# Microcontroller.net
KiCad netlist of a schematic drawn in Altium Designer
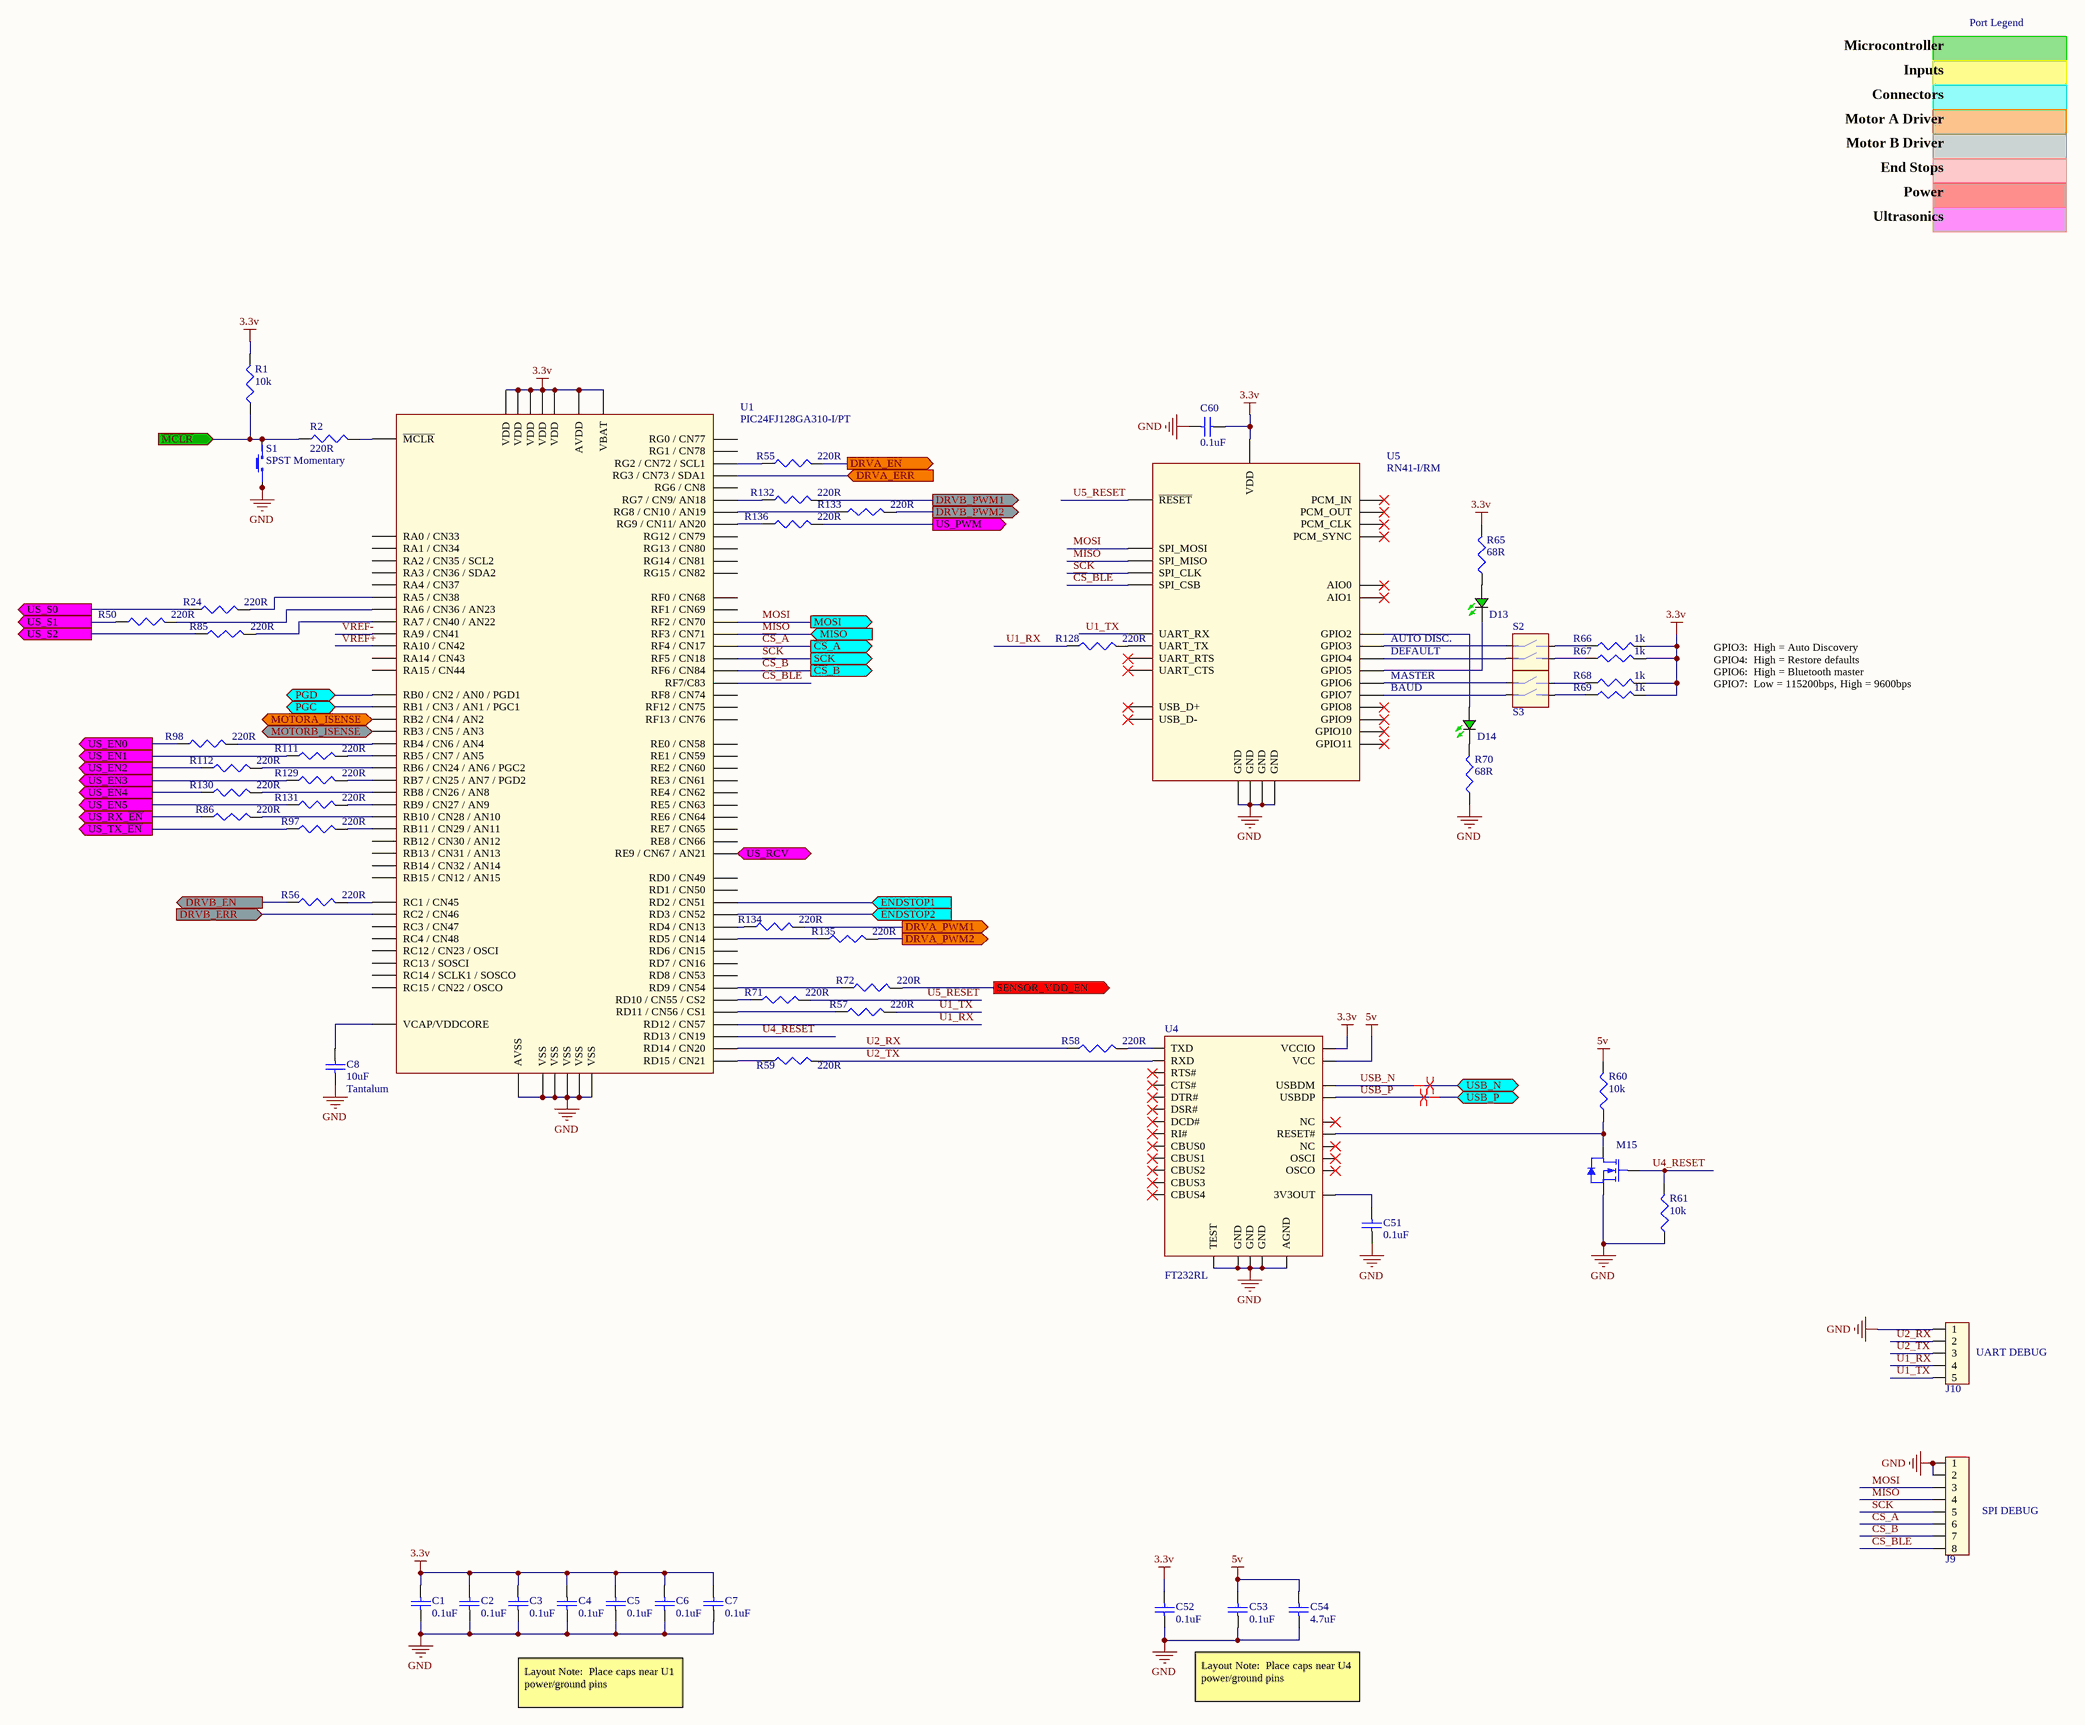
[diagram p0: Microcontroller.SchDoc]

(export (version "E")
  (design (tool "Eeschema 10.0.6"))
  (components
    (comp (ref "C1") (value "0.1uF") (footprint "CAP0603W") (libsource (lib "Altium Library") (part "0.1uF")))
    (comp (ref "C2") (value "0.1uF") (footprint "CAP0603W") (libsource (lib "Altium Library") (part "0.1uF")))
    (comp (ref "C3") (value "0.1uF") (footprint "CAP0603W") (libsource (lib "Altium Library") (part "0.1uF")))
    (comp (ref "C4") (value "0.1uF") (footprint "CAP0603W") (libsource (lib "Altium Library") (part "0.1uF")))
    (comp (ref "C5") (value "0.1uF") (footprint "CAP0603W") (libsource (lib "Altium Library") (part "0.1uF")))
    (comp (ref "C6") (value "0.1uF") (footprint "CAP0603W") (libsource (lib "Altium Library") (part "0.1uF")))
    (comp (ref "C7") (value "0.1uF") (footprint "CAP0603W") (libsource (lib "Altium Library") (part "0.1uF")))
    (comp (ref "C8")
      (value "10uF")
      (footprint "CAP1206W")
      (fields (field (name "TYPE") "Tantalum"))
      (libsource (lib "Altium Library") (part "10uF Tantalum"))
    )
    (comp (ref "C51")
      (value "0.1uF")
      (footprint "CAP0603W")
      (libsource (lib "Altium Library") (part "0.1uF"))
    )
    (comp (ref "C52")
      (value "0.1uF")
      (footprint "CAP0603W")
      (libsource (lib "Altium Library") (part "0.1uF"))
    )
    (comp (ref "C53")
      (value "0.1uF")
      (footprint "CAP0603W")
      (libsource (lib "Altium Library") (part "0.1uF"))
    )
    (comp (ref "C54")
      (value "4.7uF")
      (footprint "CAP1206W")
      (fields (field (name "VOLTAGE") "16v"))
      (libsource (lib "Altium Library") (part "4.7uF"))
    )
    (comp (ref "C60")
      (value "0.1uF")
      (footprint "CAP0603W")
      (libsource (lib "Altium Library") (part "0.1uF"))
    )
    (comp (ref "D13")
      (value "LTST-S270KGKT")
      (footprint "LED Green 0603")
      (fields (field (name "MFG") "Lite On"))
      (libsource (lib "Altium Library") (part "LED Green 0603"))
    )
    (comp (ref "D14")
      (value "LTST-S270KGKT")
      (footprint "LED Green 0603")
      (fields (field (name "MFG") "Lite On"))
      (libsource (lib "Altium Library") (part "LED Green 0603"))
    )
    (comp (ref "J9")
      (value "1x8 Header")
      (footprint "1x8 Header")
      (description "1x8 Header, 2.52mm pitch")
      (libsource (lib "Altium Library") (part "1x8 Header"))
    )
    (comp (ref "J10")
      (value "1x5 Header")
      (footprint "1x5 Header")
      (description "1x5 Header, 2.52mm pitch")
      (libsource (lib "Altium Library") (part "1x5 Header"))
    )
    (comp (ref "M15")
      (value "2N7002P,215")
      (footprint "SOT23-3M")
      (description "NFET_SINGLE_360mA_60V")
      (fields (field (name "MFG") "NXP"))
      (libsource (lib "Altium Library") (part "2N7002"))
    )
    (comp (ref "R1")
      (value "10k")
      (footprint "RES0603W")
      (fields (field (name "TOLERANCE") "1%") (field (name "POWER") "0.1W") (field (name "MFG") "Vishay"))
      (libsource (lib "Altium Library") (part "10K (0603)"))
    )
    (comp (ref "R2")
      (value "220R")
      (footprint "RES0603W")
      (fields (field (name "TOLERANCE") "1%") (field (name "POWER") "0.1W") (field (name "MFG") "Vishay"))
      (libsource (lib "Altium Library") (part "220R (0603)"))
    )
    (comp (ref "R24")
      (value "220R")
      (footprint "RES0603W")
      (fields (field (name "TOLERANCE") "1%") (field (name "POWER") "0.1W") (field (name "MFG") "Vishay"))
      (libsource (lib "Altium Library") (part "220R (0603)"))
    )
    (comp (ref "R50")
      (value "220R")
      (footprint "RES0603W")
      (fields (field (name "TOLERANCE") "1%") (field (name "POWER") "0.1W") (field (name "MFG") "Vishay"))
      (libsource (lib "Altium Library") (part "220R (0603)"))
    )
    (comp (ref "R55")
      (value "220R")
      (footprint "RES0603W")
      (fields (field (name "TOLERANCE") "1%") (field (name "POWER") "0.1W") (field (name "MFG") "Vishay"))
      (libsource (lib "Altium Library") (part "220R (0603)"))
    )
    (comp (ref "R56")
      (value "220R")
      (footprint "RES0603W")
      (fields (field (name "TOLERANCE") "1%") (field (name "POWER") "0.1W") (field (name "MFG") "Vishay"))
      (libsource (lib "Altium Library") (part "220R (0603)"))
    )
    (comp (ref "R57")
      (value "220R")
      (footprint "RES0603W")
      (fields (field (name "TOLERANCE") "1%") (field (name "POWER") "0.1W") (field (name "MFG") "Vishay"))
      (libsource (lib "Altium Library") (part "220R (0603)"))
    )
    (comp (ref "R58")
      (value "220R")
      (footprint "RES0603W")
      (fields (field (name "TOLERANCE") "1%") (field (name "POWER") "0.1W") (field (name "MFG") "Vishay"))
      (libsource (lib "Altium Library") (part "220R (0603)"))
    )
    (comp (ref "R59")
      (value "220R")
      (footprint "RES0603W")
      (fields (field (name "TOLERANCE") "1%") (field (name "POWER") "0.1W") (field (name "MFG") "Vishay"))
      (libsource (lib "Altium Library") (part "220R (0603)"))
    )
    (comp (ref "R60")
      (value "10k")
      (footprint "RES0603W")
      (fields (field (name "TOLERANCE") "1%") (field (name "POWER") "0.1W") (field (name "MFG") "Vishay"))
      (libsource (lib "Altium Library") (part "10K (0603)"))
    )
    (comp (ref "R61")
      (value "10k")
      (footprint "RES0603W")
      (fields (field (name "TOLERANCE") "1%") (field (name "POWER") "0.1W") (field (name "MFG") "Vishay"))
      (libsource (lib "Altium Library") (part "10K (0603)"))
    )
    (comp (ref "R65")
      (value "68R")
      (footprint "RES0603W")
      (fields (field (name "TOLERANCE") "1%") (field (name "POWER") "0.1W") (field (name "MFG") "Vishay"))
      (libsource (lib "Altium Library") (part "68R (0603)"))
    )
    (comp (ref "R66")
      (value "1k")
      (footprint "RES0603W")
      (fields (field (name "TOLERANCE") "1%") (field (name "POWER") "0.1W") (field (name "MFG") "Vishay"))
      (libsource (lib "Altium Library") (part "1k (0603)"))
    )
    (comp (ref "R67")
      (value "1k")
      (footprint "RES0603W")
      (fields (field (name "TOLERANCE") "1%") (field (name "POWER") "0.1W") (field (name "MFG") "Vishay"))
      (libsource (lib "Altium Library") (part "1k (0603)"))
    )
    (comp (ref "R68")
      (value "1k")
      (footprint "RES0603W")
      (fields (field (name "TOLERANCE") "1%") (field (name "POWER") "0.1W") (field (name "MFG") "Vishay"))
      (libsource (lib "Altium Library") (part "1k (0603)"))
    )
    (comp (ref "R69")
      (value "1k")
      (footprint "RES0603W")
      (fields (field (name "TOLERANCE") "1%") (field (name "POWER") "0.1W") (field (name "MFG") "Vishay"))
      (libsource (lib "Altium Library") (part "1k (0603)"))
    )
    (comp (ref "R70")
      (value "68R")
      (footprint "RES0603W")
      (fields (field (name "TOLERANCE") "1%") (field (name "POWER") "0.1W") (field (name "MFG") "Vishay"))
      (libsource (lib "Altium Library") (part "68R (0603)"))
    )
    (comp (ref "R71")
      (value "220R")
      (footprint "RES0603W")
      (fields (field (name "TOLERANCE") "1%") (field (name "POWER") "0.1W") (field (name "MFG") "Vishay"))
      (libsource (lib "Altium Library") (part "220R (0603)"))
    )
    (comp (ref "R72")
      (value "220R")
      (footprint "RES0603W")
      (fields (field (name "TOLERANCE") "1%") (field (name "POWER") "0.1W") (field (name "MFG") "Vishay"))
      (libsource (lib "Altium Library") (part "220R (0603)"))
    )
    (comp (ref "R85")
      (value "220R")
      (footprint "RES0603W")
      (fields (field (name "TOLERANCE") "1%") (field (name "POWER") "0.1W") (field (name "MFG") "Vishay"))
      (libsource (lib "Altium Library") (part "220R (0603)"))
    )
    (comp (ref "R86")
      (value "220R")
      (footprint "RES0603W")
      (fields (field (name "TOLERANCE") "1%") (field (name "POWER") "0.1W") (field (name "MFG") "Vishay"))
      (libsource (lib "Altium Library") (part "220R (0603)"))
    )
    (comp (ref "R97")
      (value "220R")
      (footprint "RES0603W")
      (fields (field (name "TOLERANCE") "1%") (field (name "POWER") "0.1W") (field (name "MFG") "Vishay"))
      (libsource (lib "Altium Library") (part "220R (0603)"))
    )
    (comp (ref "R98")
      (value "220R")
      (footprint "RES0603W")
      (fields (field (name "TOLERANCE") "1%") (field (name "POWER") "0.1W") (field (name "MFG") "Vishay"))
      (libsource (lib "Altium Library") (part "220R (0603)"))
    )
    (comp (ref "R111")
      (value "220R")
      (footprint "RES0603W")
      (fields (field (name "TOLERANCE") "1%") (field (name "POWER") "0.1W") (field (name "MFG") "Vishay"))
      (libsource (lib "Altium Library") (part "220R (0603)"))
    )
    (comp (ref "R112")
      (value "220R")
      (footprint "RES0603W")
      (fields (field (name "TOLERANCE") "1%") (field (name "POWER") "0.1W") (field (name "MFG") "Vishay"))
      (libsource (lib "Altium Library") (part "220R (0603)"))
    )
    (comp (ref "R128")
      (value "220R")
      (footprint "RES0603W")
      (fields (field (name "TOLERANCE") "1%") (field (name "POWER") "0.1W") (field (name "MFG") "Vishay"))
      (libsource (lib "Altium Library") (part "220R (0603)"))
    )
    (comp (ref "R129")
      (value "220R")
      (footprint "RES0603W")
      (fields (field (name "TOLERANCE") "1%") (field (name "POWER") "0.1W") (field (name "MFG") "Vishay"))
      (libsource (lib "Altium Library") (part "220R (0603)"))
    )
    (comp (ref "R130")
      (value "220R")
      (footprint "RES0603W")
      (fields (field (name "TOLERANCE") "1%") (field (name "POWER") "0.1W") (field (name "MFG") "Vishay"))
      (libsource (lib "Altium Library") (part "220R (0603)"))
    )
    (comp (ref "R131")
      (value "220R")
      (footprint "RES0603W")
      (fields (field (name "TOLERANCE") "1%") (field (name "POWER") "0.1W") (field (name "MFG") "Vishay"))
      (libsource (lib "Altium Library") (part "220R (0603)"))
    )
    (comp (ref "R132")
      (value "220R")
      (footprint "RES0603W")
      (fields (field (name "TOLERANCE") "1%") (field (name "POWER") "0.1W") (field (name "MFG") "Vishay"))
      (libsource (lib "Altium Library") (part "220R (0603)"))
    )
    (comp (ref "R133")
      (value "220R")
      (footprint "RES0603W")
      (fields (field (name "TOLERANCE") "1%") (field (name "POWER") "0.1W") (field (name "MFG") "Vishay"))
      (libsource (lib "Altium Library") (part "220R (0603)"))
    )
    (comp (ref "R134")
      (value "220R")
      (footprint "RES0603W")
      (fields (field (name "TOLERANCE") "1%") (field (name "POWER") "0.1W") (field (name "MFG") "Vishay"))
      (libsource (lib "Altium Library") (part "220R (0603)"))
    )
    (comp (ref "R135")
      (value "220R")
      (footprint "RES0603W")
      (fields (field (name "TOLERANCE") "1%") (field (name "POWER") "0.1W") (field (name "MFG") "Vishay"))
      (libsource (lib "Altium Library") (part "220R (0603)"))
    )
    (comp (ref "R136")
      (value "220R")
      (footprint "RES0603W")
      (fields (field (name "TOLERANCE") "1%") (field (name "POWER") "0.1W") (field (name "MFG") "Vishay"))
      (libsource (lib "Altium Library") (part "220R (0603)"))
    )
    (comp (ref "S1")
      (value "SPST Momentary")
      (footprint "TECONN_1571563")
      (description "SPST Momentary Switch")
      (fields (field (name "MFG") "TE Connectivity") (field (name "TYPE") "SPST Momentary"))
      (libsource (lib "Altium Library") (part "SPST Momentary"))
    )
    (comp (ref "S2")
      (value "SPST")
      (footprint "CTS_219-2MST")
      (description "SPST Microswitch Array (2 Switches)")
      (fields (field (name "MFG") "CTS"))
      (libsource (lib "Altium Library") (part "2xSPST Microswitch"))
    )
    (comp (ref "S3")
      (value "SPST")
      (footprint "CTS_219-2MST")
      (description "SPST Microswitch Array (2 Switches)")
      (fields (field (name "MFG") "CTS"))
      (libsource (lib "Altium Library") (part "2xSPST Microswitch"))
    )
    (comp (ref "U1")
      (value "PIC24FJ128GA310-I/PT")
      (footprint "TQFP100 0.4mm Pitch")
      (fields (field (name "MFG") "Microchip"))
      (libsource (lib "Altium Library") (part "PIC24FJ128GA310"))
    )
    (comp (ref "U4")
      (value "FT232RL")
      (footprint "SSOP-28")
      (description "UART Interface/Bridge")
      (fields (field (name "MFG") "FTDI"))
      (libsource (lib "Altium Library") (part "FT232RL"))
    )
    (comp (ref "U5")
      (value "RN41-I/RM")
      (footprint "RN41")
      (description "2.4GHz Class 1 Bluetooth Module")
      (fields (field (name "MFG") "MICROCHIP"))
      (libsource (lib "Altium Library") (part "RN41"))
    )
  )
  (nets
    (net (code "1") (name "/DRVA_EN") (class "Default")
      (node (ref "R55") (pin "2") (pinfunction "2_2") (pintype "passive"))
    )
    (net (code "2") (name "/DRVA_ERR") (class "Default")
      (node (ref "U1") (pin "56") (pinfunction "RG3_/_CN73_/_SDA1_56") (pintype "passive"))
    )
    (net (code "3") (name "/DRVA_PWM1") (class "Default")
      (node (ref "R134") (pin "2") (pinfunction "2_2") (pintype "passive"))
    )
    (net (code "4") (name "/DRVA_PWM2") (class "Default")
      (node (ref "R135") (pin "2") (pinfunction "2_2") (pintype "passive"))
    )
    (net (code "5") (name "/DRVB_EN") (class "Default")
      (node (ref "R56") (pin "1") (pinfunction "1_1") (pintype "passive"))
    )
    (net (code "6") (name "/DRVB_ERR") (class "Default")
      (node (ref "U1") (pin "7") (pinfunction "RC2_/_CN46_7") (pintype "passive"))
    )
    (net (code "7") (name "/DRVB_PWM1") (class "Default")
      (node (ref "R132") (pin "2") (pinfunction "2_2") (pintype "passive"))
    )
    (net (code "8") (name "/DRVB_PWM2") (class "Default")
      (node (ref "R133") (pin "2") (pinfunction "2_2") (pintype "passive"))
    )
    (net (code "9") (name "/ENDSTOP1") (class "Default")
      (node (ref "U1") (pin "77") (pinfunction "RD2_/_CN51_77") (pintype "passive"))
    )
    (net (code "10") (name "/ENDSTOP2") (class "Default")
      (node (ref "U1") (pin "78") (pinfunction "RD3_/_CN52_78") (pintype "passive"))
    )
    (net (code "11") (name "/MISO") (class "Default")
      (node (ref "J9") (pin "4") (pinfunction "4_4") (pintype "passive"))
      (node (ref "U1") (pin "51") (pinfunction "RF3_/_CN71_51") (pintype "passive"))
      (node (ref "U5") (pin "24") (pinfunction "SPI_MISO_24") (pintype "passive"))
    )
    (net (code "12") (name "/MOSI") (class "Default")
      (node (ref "J9") (pin "3") (pinfunction "3_3") (pintype "passive"))
      (node (ref "U1") (pin "52") (pinfunction "RF2_/_CN70_52") (pintype "passive"))
      (node (ref "U5") (pin "2") (pinfunction "SPI_MOSI_2") (pintype "passive"))
    )
    (net (code "13") (name "/MOTORA_ISENSE") (class "Default")
      (node (ref "U1") (pin "23") (pinfunction "RB2_/_CN4_/_AN2_23") (pintype "passive"))
    )
    (net (code "14") (name "/MOTORB_ISENSE") (class "Default")
      (node (ref "U1") (pin "22") (pinfunction "RB3_/_CN5_/_AN3_22") (pintype "passive"))
    )
    (net (code "15") (name "/PGC") (class "Default")
      (node (ref "U1") (pin "24") (pinfunction "RB1_/_CN3_/_AN1_/_PGC1_24") (pintype "passive"))
    )
    (net (code "16") (name "/PGD") (class "Default")
      (node (ref "U1") (pin "25") (pinfunction "RB0_/_CN2_/_AN0_/_PGD1_25") (pintype "passive"))
    )
    (net (code "17") (name "/SCK") (class "Default")
      (node (ref "J9") (pin "5") (pinfunction "5_5") (pintype "passive"))
      (node (ref "U1") (pin "50") (pinfunction "RF5_/_CN18_50") (pintype "passive"))
      (node (ref "U5") (pin "6") (pinfunction "SPI_CLK_6") (pintype "passive"))
    )
    (net (code "18") (name "/SENSOR_VDD_EN") (class "Default")
      (node (ref "R72") (pin "2") (pinfunction "2_2") (pintype "passive"))
    )
    (net (code "19") (name "/U1_RX") (class "Default")
      (node (ref "J10") (pin "4") (pinfunction "4_4") (pintype "passive"))
      (node (ref "R128") (pin "1") (pinfunction "1_1") (pintype "passive"))
      (node (ref "U1") (pin "79") (pinfunction "RD12_/_CN57_79") (pintype "passive"))
    )
    (net (code "20") (name "/U1_TX") (class "Default")
      (node (ref "J10") (pin "5") (pinfunction "5_5") (pintype "passive"))
      (node (ref "R57") (pin "2") (pinfunction "2_2") (pintype "passive"))
      (node (ref "U5") (pin "13") (pinfunction "UART_RX_13") (pintype "passive"))
    )
    (net (code "21") (name "/U2_RX") (class "Default")
      (node (ref "J10") (pin "2") (pinfunction "2_2") (pintype "passive"))
      (node (ref "R58") (pin "1") (pinfunction "1_1") (pintype "passive"))
      (node (ref "U1") (pin "47") (pinfunction "RD14_/_CN20_47") (pintype "passive"))
    )
    (net (code "22") (name "/U2_TX") (class "Default")
      (node (ref "J10") (pin "3") (pinfunction "3_3") (pintype "passive"))
      (node (ref "R59") (pin "2") (pinfunction "2_2") (pintype "passive"))
      (node (ref "U4") (pin "5") (pinfunction "RXD_5") (pintype "passive"))
    )
    (net (code "23") (name "/U4_RESET") (class "Default")
      (node (ref "M15") (pin "1") (pinfunction "GATE_1") (pintype "passive"))
      (node (ref "R61") (pin "2") (pinfunction "2_2") (pintype "passive"))
      (node (ref "U1") (pin "80") (pinfunction "RD13_/_CN19_80") (pintype "passive"))
    )
    (net (code "24") (name "/U5_RESET") (class "Default")
      (node (ref "R71") (pin "2") (pinfunction "2_2") (pintype "passive"))
      (node (ref "U5") (pin "5") (pinfunction "~{RESET}_5") (pintype "passive"))
    )
    (net (code "25") (name "/USB_N") (class "Default")
      (node (ref "U4") (pin "16") (pinfunction "USBDM_16") (pintype "passive"))
    )
    (net (code "26") (name "/USB_P") (class "Default")
      (node (ref "U4") (pin "15") (pinfunction "USBDP_15") (pintype "passive"))
    )
    (net (code "27") (name "/US_EN0") (class "Default")
      (node (ref "R98") (pin "1") (pinfunction "1_1") (pintype "passive"))
    )
    (net (code "28") (name "/US_EN1") (class "Default")
      (node (ref "R111") (pin "1") (pinfunction "1_1") (pintype "passive"))
    )
    (net (code "29") (name "/US_EN2") (class "Default")
      (node (ref "R112") (pin "1") (pinfunction "1_1") (pintype "passive"))
    )
    (net (code "30") (name "/US_EN3") (class "Default")
      (node (ref "R129") (pin "1") (pinfunction "1_1") (pintype "passive"))
    )
    (net (code "31") (name "/US_EN4") (class "Default")
      (node (ref "R130") (pin "1") (pinfunction "1_1") (pintype "passive"))
    )
    (net (code "32") (name "/US_EN5") (class "Default")
      (node (ref "R131") (pin "1") (pinfunction "1_1") (pintype "passive"))
    )
    (net (code "33") (name "/US_PWM") (class "Default")
      (node (ref "R136") (pin "2") (pinfunction "2_2") (pintype "passive"))
    )
    (net (code "34") (name "/US_RCV") (class "Default")
      (node (ref "U1") (pin "19") (pinfunction "RE9_/_CN67_/_AN21_19") (pintype "passive"))
    )
    (net (code "35") (name "/US_RX_~{EN}") (class "Default")
      (node (ref "R86") (pin "1") (pinfunction "1_1") (pintype "passive"))
    )
    (net (code "36") (name "/US_S0") (class "Default")
      (node (ref "R24") (pin "1") (pinfunction "1_1") (pintype "passive"))
    )
    (net (code "37") (name "/US_S1") (class "Default")
      (node (ref "R50") (pin "1") (pinfunction "1_1") (pintype "passive"))
    )
    (net (code "38") (name "/US_S2") (class "Default")
      (node (ref "R85") (pin "1") (pinfunction "1_1") (pintype "passive"))
    )
    (net (code "39") (name "/US_TX_~{EN}") (class "Default")
      (node (ref "R97") (pin "1") (pinfunction "1_1") (pintype "passive"))
    )
    (net (code "40") (name "/VREF+") (class "Default")
      (node (ref "U1") (pin "29") (pinfunction "RA10_/_CN42_29") (pintype "passive"))
    )
    (net (code "41") (name "/VREF-") (class "Default")
      (node (ref "U1") (pin "28") (pinfunction "RA9_/_CN41_28") (pintype "passive"))
    )
    (net (code "42") (name "/~{CS}_A") (class "Default")
      (node (ref "J9") (pin "6") (pinfunction "6_6") (pintype "passive"))
      (node (ref "U1") (pin "49") (pinfunction "RF4_/_CN17_49") (pintype "passive"))
    )
    (net (code "43") (name "/~{CS}_B") (class "Default")
      (node (ref "J9") (pin "7") (pinfunction "7_7") (pintype "passive"))
      (node (ref "U1") (pin "55") (pinfunction "RF6_/_CN84_55") (pintype "passive"))
    )
    (net (code "44") (name "/~{CS}_BLE") (class "Default")
      (node (ref "J9") (pin "8") (pinfunction "8_8") (pintype "passive"))
      (node (ref "U1") (pin "54") (pinfunction "RF7/C83_54") (pintype "passive"))
      (node (ref "U5") (pin "23") (pinfunction "SPI_CSB_23") (pintype "passive"))
    )
    (net (code "45") (name "/~{MCLR}") (class "Default")
      (node (ref "R1") (pin "1") (pinfunction "1_1") (pintype "passive"))
      (node (ref "R2") (pin "1") (pinfunction "1_1") (pintype "passive"))
      (node (ref "S1") (pin "3") (pinfunction "3_3") (pintype "passive"))
      (node (ref "S1") (pin "4") (pinfunction "4_4") (pintype "passive"))
    )
    (net (code "46") (name "3.3v") (class "Default")
      (node (ref "C1") (pin "1") (pinfunction "1_1") (pintype "passive"))
      (node (ref "C2") (pin "1") (pinfunction "1_1") (pintype "passive"))
      (node (ref "C3") (pin "1") (pinfunction "1_1") (pintype "passive"))
      (node (ref "C4") (pin "1") (pinfunction "1_1") (pintype "passive"))
      (node (ref "C5") (pin "1") (pinfunction "1_1") (pintype "passive"))
      (node (ref "C52") (pin "1") (pinfunction "1_1") (pintype "passive"))
      (node (ref "C6") (pin "1") (pinfunction "1_1") (pintype "passive"))
      (node (ref "C60") (pin "2") (pinfunction "2_2") (pintype "passive"))
      (node (ref "C7") (pin "1") (pinfunction "1_1") (pintype "passive"))
      (node (ref "R1") (pin "2") (pinfunction "2_2") (pintype "passive"))
      (node (ref "R65") (pin "2") (pinfunction "2_2") (pintype "passive"))
      (node (ref "R66") (pin "2") (pinfunction "2_2") (pintype "passive"))
      (node (ref "R67") (pin "2") (pinfunction "2_2") (pintype "passive"))
      (node (ref "R68") (pin "2") (pinfunction "2_2") (pintype "passive"))
      (node (ref "R69") (pin "2") (pinfunction "2_2") (pintype "passive"))
      (node (ref "U1") (pin "16") (pinfunction "VDD_16") (pintype "passive"))
      (node (ref "U1") (pin "2") (pinfunction "VDD_2") (pintype "passive"))
      (node (ref "U1") (pin "30") (pinfunction "AVDD_30") (pintype "passive"))
      (node (ref "U1") (pin "37") (pinfunction "VDD_37") (pintype "passive"))
      (node (ref "U1") (pin "46") (pinfunction "VDD_46") (pintype "passive"))
      (node (ref "U1") (pin "62") (pinfunction "VDD_62") (pintype "passive"))
      (node (ref "U1") (pin "86") (pinfunction "VBAT_86") (pintype "passive"))
      (node (ref "U4") (pin "4") (pinfunction "VCCIO_4") (pintype "passive"))
      (node (ref "U5") (pin "11") (pinfunction "VDD_11") (pintype "passive"))
    )
    (net (code "47") (name "5v") (class "Default")
      (node (ref "C53") (pin "1") (pinfunction "1_1") (pintype "passive"))
      (node (ref "C54") (pin "1") (pinfunction "1_1") (pintype "passive"))
      (node (ref "R60") (pin "2") (pinfunction "2_2") (pintype "passive"))
      (node (ref "U4") (pin "20") (pinfunction "VCC_20") (pintype "passive"))
    )
    (net (code "48") (name "GND") (class "Default")
      (node (ref "C1") (pin "2") (pinfunction "2_2") (pintype "passive"))
      (node (ref "C2") (pin "2") (pinfunction "2_2") (pintype "passive"))
      (node (ref "C3") (pin "2") (pinfunction "2_2") (pintype "passive"))
      (node (ref "C4") (pin "2") (pinfunction "2_2") (pintype "passive"))
      (node (ref "C5") (pin "2") (pinfunction "2_2") (pintype "passive"))
      (node (ref "C51") (pin "2") (pinfunction "2_2") (pintype "passive"))
      (node (ref "C52") (pin "2") (pinfunction "2_2") (pintype "passive"))
      (node (ref "C53") (pin "2") (pinfunction "2_2") (pintype "passive"))
      (node (ref "C54") (pin "2") (pinfunction "2_2") (pintype "passive"))
      (node (ref "C6") (pin "2") (pinfunction "2_2") (pintype "passive"))
      (node (ref "C60") (pin "1") (pinfunction "1_1") (pintype "passive"))
      (node (ref "C7") (pin "2") (pinfunction "2_2") (pintype "passive"))
      (node (ref "C8") (pin "2") (pinfunction "2_2") (pintype "passive"))
      (node (ref "J10") (pin "1") (pinfunction "1_1") (pintype "passive"))
      (node (ref "J9") (pin "1") (pinfunction "1_1") (pintype "passive"))
      (node (ref "J9") (pin "2") (pinfunction "2_2") (pintype "passive"))
      (node (ref "M15") (pin "2") (pinfunction "SOURCE_2") (pintype "passive"))
      (node (ref "R61") (pin "1") (pinfunction "1_1") (pintype "passive"))
      (node (ref "R70") (pin "1") (pinfunction "1_1") (pintype "passive"))
      (node (ref "S1") (pin "1") (pinfunction "1_1") (pintype "passive"))
      (node (ref "S1") (pin "2") (pinfunction "2_2") (pintype "passive"))
      (node (ref "U1") (pin "15") (pinfunction "VSS_15") (pintype "passive"))
      (node (ref "U1") (pin "31") (pinfunction "AVSS_31") (pintype "passive"))
      (node (ref "U1") (pin "36") (pinfunction "VSS_36") (pintype "passive"))
      (node (ref "U1") (pin "45") (pinfunction "VSS_45") (pintype "passive"))
      (node (ref "U1") (pin "65") (pinfunction "VSS_65") (pintype "passive"))
      (node (ref "U1") (pin "75") (pinfunction "VSS_75") (pintype "passive"))
      (node (ref "U4") (pin "18") (pinfunction "GND_18") (pintype "passive"))
      (node (ref "U4") (pin "21") (pinfunction "GND_21") (pintype "passive"))
      (node (ref "U4") (pin "25") (pinfunction "AGND_25") (pintype "passive"))
      (node (ref "U4") (pin "26") (pinfunction "TEST_26") (pintype "passive"))
      (node (ref "U4") (pin "7") (pinfunction "GND_7") (pintype "passive"))
      (node (ref "U5") (pin "1") (pinfunction "GND_1") (pintype "passive"))
      (node (ref "U5") (pin "12") (pinfunction "GND_12") (pintype "passive"))
      (node (ref "U5") (pin "28") (pinfunction "GND_28") (pintype "passive"))
      (node (ref "U5") (pin "29") (pinfunction "GND_29") (pintype "passive"))
    )
    (net (code "49") (name "Net-(D13-A)") (class "Default")
      (node (ref "D13") (pin "2") (pinfunction "A_2") (pintype "passive"))
      (node (ref "R65") (pin "1") (pinfunction "1_1") (pintype "passive"))
    )
    (net (code "50") (name "Net-(D13-K)") (class "Default")
      (node (ref "D13") (pin "1") (pinfunction "K_1") (pintype "passive"))
      (node (ref "U5") (pin "21") (pinfunction "GPIO5_21") (pintype "passive"))
    )
    (net (code "51") (name "Net-(D14-A)") (class "Default")
      (node (ref "D14") (pin "2") (pinfunction "A_2") (pintype "passive"))
      (node (ref "U5") (pin "19") (pinfunction "GPIO2_19") (pintype "passive"))
    )
    (net (code "52") (name "Net-(D14-K)") (class "Default")
      (node (ref "D14") (pin "1") (pinfunction "K_1") (pintype "passive"))
      (node (ref "R70") (pin "2") (pinfunction "2_2") (pintype "passive"))
    )
    (net (code "53") (name "Net-(R66-Pad1)") (class "Default")
      (node (ref "R66") (pin "1") (pinfunction "1_1") (pintype "passive"))
      (node (ref "S2") (pin "2") (pinfunction "2_2") (pintype "power_in"))
    )
    (net (code "54") (name "Net-(R67-Pad1)") (class "Default")
      (node (ref "R67") (pin "1") (pinfunction "1_1") (pintype "passive"))
      (node (ref "S2") (pin "4") (pinfunction "4_4") (pintype "power_in"))
    )
    (net (code "55") (name "Net-(R68-Pad1)") (class "Default")
      (node (ref "R68") (pin "1") (pinfunction "1_1") (pintype "passive"))
      (node (ref "S3") (pin "2") (pinfunction "2_2") (pintype "power_in"))
    )
    (net (code "56") (name "Net-(R69-Pad1)") (class "Default")
      (node (ref "R69") (pin "1") (pinfunction "1_1") (pintype "passive"))
      (node (ref "S3") (pin "4") (pinfunction "4_4") (pintype "power_in"))
    )
    (net (code "57") (name "Net-(U1-RA5_{slash}_CN38)") (class "Default")
      (node (ref "R24") (pin "2") (pinfunction "2_2") (pintype "passive"))
      (node (ref "U1") (pin "61") (pinfunction "RA5_/_CN38_61") (pintype "passive"))
    )
    (net (code "58") (name "Net-(U1-RA6_{slash}_CN36_{slash}_AN23)") (class "Default")
      (node (ref "R50") (pin "2") (pinfunction "2_2") (pintype "passive"))
      (node (ref "U1") (pin "91") (pinfunction "RA6_/_CN36_/_AN23_91") (pintype "passive"))
    )
    (net (code "59") (name "Net-(U1-RA7_{slash}_CN40_{slash}_AN22)") (class "Default")
      (node (ref "R85") (pin "2") (pinfunction "2_2") (pintype "passive"))
      (node (ref "U1") (pin "92") (pinfunction "RA7_/_CN40_/_AN22_92") (pintype "passive"))
    )
    (net (code "60") (name "Net-(U1-RB4_{slash}_CN6_{slash}_AN4)") (class "Default")
      (node (ref "R98") (pin "2") (pinfunction "2_2") (pintype "passive"))
      (node (ref "U1") (pin "21") (pinfunction "RB4_/_CN6_/_AN4_21") (pintype "passive"))
    )
    (net (code "61") (name "Net-(U1-RB5_{slash}_CN7_{slash}_AN5)") (class "Default")
      (node (ref "R111") (pin "2") (pinfunction "2_2") (pintype "passive"))
      (node (ref "U1") (pin "20") (pinfunction "RB5_/_CN7_/_AN5_20") (pintype "passive"))
    )
    (net (code "62") (name "Net-(U1-RB6_{slash}_CN24_{slash}_AN6_{slash}_PGC2)") (class "Default")
      (node (ref "R112") (pin "2") (pinfunction "2_2") (pintype "passive"))
      (node (ref "U1") (pin "26") (pinfunction "RB6_/_CN24_/_AN6_/_PGC2_26") (pintype "passive"))
    )
    (net (code "63") (name "Net-(U1-RB7_{slash}_CN25_{slash}_AN7_{slash}_PGD2)") (class "Default")
      (node (ref "R129") (pin "2") (pinfunction "2_2") (pintype "passive"))
      (node (ref "U1") (pin "27") (pinfunction "RB7_/_CN25_/_AN7_/_PGD2_27") (pintype "passive"))
    )
    (net (code "64") (name "Net-(U1-RB8_{slash}_CN26_{slash}_AN8)") (class "Default")
      (node (ref "R130") (pin "2") (pinfunction "2_2") (pintype "passive"))
      (node (ref "U1") (pin "32") (pinfunction "RB8_/_CN26_/_AN8_32") (pintype "passive"))
    )
    (net (code "65") (name "Net-(U1-RB9_{slash}_CN27_{slash}_AN9)") (class "Default")
      (node (ref "R131") (pin "2") (pinfunction "2_2") (pintype "passive"))
      (node (ref "U1") (pin "33") (pinfunction "RB9_/_CN27_/_AN9_33") (pintype "passive"))
    )
    (net (code "66") (name "Net-(U1-RB10_{slash}_CN28_{slash}_AN10)") (class "Default")
      (node (ref "R86") (pin "2") (pinfunction "2_2") (pintype "passive"))
      (node (ref "U1") (pin "34") (pinfunction "RB10_/_CN28_/_AN10_34") (pintype "passive"))
    )
    (net (code "67") (name "Net-(U1-RB11_{slash}_CN29_{slash}_AN11)") (class "Default")
      (node (ref "R97") (pin "2") (pinfunction "2_2") (pintype "passive"))
      (node (ref "U1") (pin "35") (pinfunction "RB11_/_CN29_/_AN11_35") (pintype "passive"))
    )
    (net (code "68") (name "Net-(U1-RC1_{slash}_CN45)") (class "Default")
      (node (ref "R56") (pin "2") (pinfunction "2_2") (pintype "passive"))
      (node (ref "U1") (pin "6") (pinfunction "RC1_/_CN45_6") (pintype "passive"))
    )
    (net (code "69") (name "Net-(U1-RD4_{slash}_CN13)") (class "Default")
      (node (ref "R134") (pin "1") (pinfunction "1_1") (pintype "passive"))
      (node (ref "U1") (pin "81") (pinfunction "RD4_/_CN13_81") (pintype "passive"))
    )
    (net (code "70") (name "Net-(U1-RD5_{slash}_CN14)") (class "Default")
      (node (ref "R135") (pin "1") (pinfunction "1_1") (pintype "passive"))
      (node (ref "U1") (pin "82") (pinfunction "RD5_/_CN14_82") (pintype "passive"))
    )
    (net (code "71") (name "Net-(U1-RD9_{slash}_CN54)") (class "Default")
      (node (ref "R72") (pin "1") (pinfunction "1_1") (pintype "passive"))
      (node (ref "U1") (pin "69") (pinfunction "RD9_/_CN54_69") (pintype "passive"))
    )
    (net (code "72") (name "Net-(U1-RD10_{slash}_CN55_{slash}_CS2)") (class "Default")
      (node (ref "R71") (pin "1") (pinfunction "1_1") (pintype "passive"))
      (node (ref "U1") (pin "70") (pinfunction "RD10_/_CN55_/_CS2_70") (pintype "passive"))
    )
    (net (code "73") (name "Net-(U1-RD11_{slash}_CN56_{slash}_CS1)") (class "Default")
      (node (ref "R57") (pin "1") (pinfunction "1_1") (pintype "passive"))
      (node (ref "U1") (pin "71") (pinfunction "RD11_/_CN56_/_CS1_71") (pintype "passive"))
    )
    (net (code "74") (name "Net-(U1-RD15_{slash}_CN21)") (class "Default")
      (node (ref "R59") (pin "1") (pinfunction "1_1") (pintype "passive"))
      (node (ref "U1") (pin "48") (pinfunction "RD15_/_CN21_48") (pintype "passive"))
    )
    (net (code "75") (name "Net-(U1-RG2_{slash}_CN72_{slash}_SCL1)") (class "Default")
      (node (ref "R55") (pin "1") (pinfunction "1_1") (pintype "passive"))
      (node (ref "U1") (pin "57") (pinfunction "RG2_/_CN72_/_SCL1_57") (pintype "passive"))
    )
    (net (code "76") (name "Net-(U1-RG7_{slash}_CN9{slash}_AN18)") (class "Default")
      (node (ref "R132") (pin "1") (pinfunction "1_1") (pintype "passive"))
      (node (ref "U1") (pin "11") (pinfunction "RG7_/_CN9/_AN18_11") (pintype "passive"))
    )
    (net (code "77") (name "Net-(U1-RG8_{slash}_CN10_{slash}_AN19)") (class "Default")
      (node (ref "R133") (pin "1") (pinfunction "1_1") (pintype "passive"))
      (node (ref "U1") (pin "12") (pinfunction "RG8_/_CN10_/_AN19_12") (pintype "passive"))
    )
    (net (code "78") (name "Net-(U1-RG9_{slash}_CN11{slash}_AN20)") (class "Default")
      (node (ref "R136") (pin "1") (pinfunction "1_1") (pintype "passive"))
      (node (ref "U1") (pin "14") (pinfunction "RG9_/_CN11/_AN20_14") (pintype "passive"))
    )
    (net (code "79") (name "Net-(U1-VCAP{slash}VDDCORE)") (class "Default")
      (node (ref "C8") (pin "1") (pinfunction "1_1") (pintype "passive"))
      (node (ref "U1") (pin "85") (pinfunction "VCAP/VDDCORE_85") (pintype "passive"))
    )
    (net (code "80") (name "Net-(U1-~{MCLR})") (class "Default")
      (node (ref "R2") (pin "2") (pinfunction "2_2") (pintype "passive"))
      (node (ref "U1") (pin "13") (pinfunction "~{MCLR}_13") (pintype "passive"))
    )
    (net (code "81") (name "Net-(U4-3V3OUT)") (class "Default")
      (node (ref "C51") (pin "1") (pinfunction "1_1") (pintype "passive"))
      (node (ref "U4") (pin "17") (pinfunction "3V3OUT_17") (pintype "passive"))
    )
    (net (code "82") (name "Net-(U4-RESET#)") (class "Default")
      (node (ref "M15") (pin "3") (pinfunction "SOURCE_3") (pintype "passive"))
      (node (ref "R60") (pin "1") (pinfunction "1_1") (pintype "passive"))
      (node (ref "U4") (pin "19") (pinfunction "RESET#_19") (pintype "passive"))
    )
    (net (code "83") (name "Net-(U4-TXD)") (class "Default")
      (node (ref "R58") (pin "2") (pinfunction "2_2") (pintype "passive"))
      (node (ref "U4") (pin "1") (pinfunction "TXD_1") (pintype "passive"))
    )
    (net (code "84") (name "Net-(U5-GPIO3)") (class "Default")
      (node (ref "S2") (pin "1") (pinfunction "1_1") (pintype "power_in"))
      (node (ref "U5") (pin "20") (pinfunction "GPIO3_20") (pintype "passive"))
    )
    (net (code "85") (name "Net-(U5-GPIO4)") (class "Default")
      (node (ref "S2") (pin "3") (pinfunction "3_3") (pintype "power_in"))
      (node (ref "U5") (pin "22") (pinfunction "GPIO4_22") (pintype "passive"))
    )
    (net (code "86") (name "Net-(U5-GPIO6)") (class "Default")
      (node (ref "S3") (pin "1") (pinfunction "1_1") (pintype "power_in"))
      (node (ref "U5") (pin "3") (pinfunction "GPIO6_3") (pintype "passive"))
    )
    (net (code "87") (name "Net-(U5-GPIO7)") (class "Default")
      (node (ref "S3") (pin "3") (pinfunction "3_3") (pintype "power_in"))
      (node (ref "U5") (pin "4") (pinfunction "GPIO7_4") (pintype "passive"))
    )
    (net (code "88") (name "Net-(U5-UART_TX)") (class "Default")
      (node (ref "R128") (pin "2") (pinfunction "2_2") (pintype "passive"))
      (node (ref "U5") (pin "14") (pinfunction "UART_TX_14") (pintype "passive"))
    )
    (net (code "89") (name "unconnected-(U1-RA0_{slash}_CN33-Pad17)") (class "Default")
      (node (ref "U1") (pin "17") (pinfunction "RA0_/_CN33_17") (pintype "passive"))
    )
    (net (code "90") (name "unconnected-(U1-RA1_{slash}_CN34-Pad38)") (class "Default")
      (node (ref "U1") (pin "38") (pinfunction "RA1_/_CN34_38") (pintype "passive"))
    )
    (net (code "91") (name "unconnected-(U1-RA2_{slash}_CN35_{slash}_SCL2-Pad58)") (class "Default")
      (node (ref "U1") (pin "58") (pinfunction "RA2_/_CN35_/_SCL2_58") (pintype "passive"))
    )
    (net (code "92") (name "unconnected-(U1-RA3_{slash}_CN36_{slash}_SDA2-Pad59)") (class "Default")
      (node (ref "U1") (pin "59") (pinfunction "RA3_/_CN36_/_SDA2_59") (pintype "passive"))
    )
    (net (code "93") (name "unconnected-(U1-RA4_{slash}_CN37-Pad60)") (class "Default")
      (node (ref "U1") (pin "60") (pinfunction "RA4_/_CN37_60") (pintype "passive"))
    )
    (net (code "94") (name "unconnected-(U1-RA14_{slash}_CN43-Pad66)") (class "Default")
      (node (ref "U1") (pin "66") (pinfunction "RA14_/_CN43_66") (pintype "passive"))
    )
    (net (code "95") (name "unconnected-(U1-RA15_{slash}_CN44-Pad67)") (class "Default")
      (node (ref "U1") (pin "67") (pinfunction "RA15_/_CN44_67") (pintype "passive"))
    )
    (net (code "96") (name "unconnected-(U1-RB12_{slash}_CN30_{slash}_AN12-Pad41)") (class "Default")
      (node (ref "U1") (pin "41") (pinfunction "RB12_/_CN30_/_AN12_41") (pintype "passive"))
    )
    (net (code "97") (name "unconnected-(U1-RB13_{slash}_CN31_{slash}_AN13-Pad42)") (class "Default")
      (node (ref "U1") (pin "42") (pinfunction "RB13_/_CN31_/_AN13_42") (pintype "passive"))
    )
    (net (code "98") (name "unconnected-(U1-RB14_{slash}_CN32_{slash}_AN14-Pad43)") (class "Default")
      (node (ref "U1") (pin "43") (pinfunction "RB14_/_CN32_/_AN14_43") (pintype "passive"))
    )
    (net (code "99") (name "unconnected-(U1-RB15_{slash}_CN12_{slash}_AN15-Pad44)") (class "Default")
      (node (ref "U1") (pin "44") (pinfunction "RB15_/_CN12_/_AN15_44") (pintype "passive"))
    )
    (net (code "100") (name "unconnected-(U1-RC3_{slash}_CN47-Pad8)") (class "Default")
      (node (ref "U1") (pin "8") (pinfunction "RC3_/_CN47_8") (pintype "passive"))
    )
    (net (code "101") (name "unconnected-(U1-RC4_{slash}_CN48-Pad9)") (class "Default")
      (node (ref "U1") (pin "9") (pinfunction "RC4_/_CN48_9") (pintype "passive"))
    )
    (net (code "102") (name "unconnected-(U1-RC12_{slash}_CN23_{slash}_OSCI-Pad63)") (class "Default")
      (node (ref "U1") (pin "63") (pinfunction "RC12_/_CN23_/_OSCI_63") (pintype "passive"))
    )
    (net (code "103") (name "unconnected-(U1-RC13_{slash}_SOSCI-Pad73)") (class "Default")
      (node (ref "U1") (pin "73") (pinfunction "RC13_/_SOSCI_73") (pintype "passive"))
    )
    (net (code "104") (name "unconnected-(U1-RC14_{slash}_SCLK1_{slash}_SOSCO-Pad74)") (class "Default")
      (node (ref "U1") (pin "74") (pinfunction "RC14_/_SCLK1_/_SOSCO_74") (pintype "passive"))
    )
    (net (code "105") (name "unconnected-(U1-RC15_{slash}_CN22_{slash}_OSCO-Pad64)") (class "Default")
      (node (ref "U1") (pin "64") (pinfunction "RC15_/_CN22_/_OSCO_64") (pintype "passive"))
    )
    (net (code "106") (name "unconnected-(U1-RD0_{slash}_CN49-Pad72)") (class "Default")
      (node (ref "U1") (pin "72") (pinfunction "RD0_/_CN49_72") (pintype "passive"))
    )
    (net (code "107") (name "unconnected-(U1-RD1_{slash}_CN50-Pad76)") (class "Default")
      (node (ref "U1") (pin "76") (pinfunction "RD1_/_CN50_76") (pintype "passive"))
    )
    (net (code "108") (name "unconnected-(U1-RD6_{slash}_CN15-Pad83)") (class "Default")
      (node (ref "U1") (pin "83") (pinfunction "RD6_/_CN15_83") (pintype "passive"))
    )
    (net (code "109") (name "unconnected-(U1-RD7_{slash}_CN16-Pad84)") (class "Default")
      (node (ref "U1") (pin "84") (pinfunction "RD7_/_CN16_84") (pintype "passive"))
    )
    (net (code "110") (name "unconnected-(U1-RD8_{slash}_CN53-Pad68)") (class "Default")
      (node (ref "U1") (pin "68") (pinfunction "RD8_/_CN53_68") (pintype "passive"))
    )
    (net (code "111") (name "unconnected-(U1-RE0_{slash}_CN58-Pad93)") (class "Default")
      (node (ref "U1") (pin "93") (pinfunction "RE0_/_CN58_93") (pintype "passive"))
    )
    (net (code "112") (name "unconnected-(U1-RE1_{slash}_CN59-Pad94)") (class "Default")
      (node (ref "U1") (pin "94") (pinfunction "RE1_/_CN59_94") (pintype "passive"))
    )
    (net (code "113") (name "unconnected-(U1-RE2_{slash}_CN60-Pad98)") (class "Default")
      (node (ref "U1") (pin "98") (pinfunction "RE2_/_CN60_98") (pintype "passive"))
    )
    (net (code "114") (name "unconnected-(U1-RE3_{slash}_CN61-Pad99)") (class "Default")
      (node (ref "U1") (pin "99") (pinfunction "RE3_/_CN61_99") (pintype "passive"))
    )
    (net (code "115") (name "unconnected-(U1-RE4_{slash}_CN62-Pad100)") (class "Default")
      (node (ref "U1") (pin "100") (pinfunction "RE4_/_CN62_100") (pintype "passive"))
    )
    (net (code "116") (name "unconnected-(U1-RE5_{slash}_CN63-Pad3)") (class "Default")
      (node (ref "U1") (pin "3") (pinfunction "RE5_/_CN63_3") (pintype "passive"))
    )
    (net (code "117") (name "unconnected-(U1-RE6_{slash}_CN64-Pad4)") (class "Default")
      (node (ref "U1") (pin "4") (pinfunction "RE6_/_CN64_4") (pintype "passive"))
    )
    (net (code "118") (name "unconnected-(U1-RE7_{slash}_CN65-Pad5)") (class "Default")
      (node (ref "U1") (pin "5") (pinfunction "RE7_/_CN65_5") (pintype "passive"))
    )
    (net (code "119") (name "unconnected-(U1-RE8_{slash}_CN66-Pad18)") (class "Default")
      (node (ref "U1") (pin "18") (pinfunction "RE8_/_CN66_18") (pintype "passive"))
    )
    (net (code "120") (name "unconnected-(U1-RF0_{slash}_CN68-Pad87)") (class "Default")
      (node (ref "U1") (pin "87") (pinfunction "RF0_/_CN68_87") (pintype "passive"))
    )
    (net (code "121") (name "unconnected-(U1-RF1_{slash}_CN69-Pad88)") (class "Default")
      (node (ref "U1") (pin "88") (pinfunction "RF1_/_CN69_88") (pintype "passive"))
    )
    (net (code "122") (name "unconnected-(U1-RF8_{slash}_CN74-Pad53)") (class "Default")
      (node (ref "U1") (pin "53") (pinfunction "RF8_/_CN74_53") (pintype "passive"))
    )
    (net (code "123") (name "unconnected-(U1-RF12_{slash}_CN75-Pad40)") (class "Default")
      (node (ref "U1") (pin "40") (pinfunction "RF12_/_CN75_40") (pintype "passive"))
    )
    (net (code "124") (name "unconnected-(U1-RF13_{slash}_CN76-Pad39)") (class "Default")
      (node (ref "U1") (pin "39") (pinfunction "RF13_/_CN76_39") (pintype "passive"))
    )
    (net (code "125") (name "unconnected-(U1-RG0_{slash}_CN77-Pad90)") (class "Default")
      (node (ref "U1") (pin "90") (pinfunction "RG0_/_CN77_90") (pintype "passive"))
    )
    (net (code "126") (name "unconnected-(U1-RG1_{slash}_CN78-Pad89)") (class "Default")
      (node (ref "U1") (pin "89") (pinfunction "RG1_/_CN78_89") (pintype "passive"))
    )
    (net (code "127") (name "unconnected-(U1-RG6_{slash}_CN8-Pad10)") (class "Default")
      (node (ref "U1") (pin "10") (pinfunction "RG6_/_CN8_10") (pintype "passive"))
    )
    (net (code "128") (name "unconnected-(U1-RG12_{slash}_CN79-Pad96)") (class "Default")
      (node (ref "U1") (pin "96") (pinfunction "RG12_/_CN79_96") (pintype "passive"))
    )
    (net (code "129") (name "unconnected-(U1-RG13_{slash}_CN80-Pad97)") (class "Default")
      (node (ref "U1") (pin "97") (pinfunction "RG13_/_CN80_97") (pintype "passive"))
    )
    (net (code "130") (name "unconnected-(U1-RG14_{slash}_CN81-Pad95)") (class "Default")
      (node (ref "U1") (pin "95") (pinfunction "RG14_/_CN81_95") (pintype "passive"))
    )
    (net (code "131") (name "unconnected-(U1-RG15_{slash}_CN82-Pad1)") (class "Default")
      (node (ref "U1") (pin "1") (pinfunction "RG15_/_CN82_1") (pintype "passive"))
    )
    (net (code "132") (name "unconnected-(U4-CBUS0-Pad23)") (class "Default")
      (node (ref "U4") (pin "23") (pinfunction "CBUS0_23") (pintype "passive+no_connect"))
    )
    (net (code "133") (name "unconnected-(U4-CBUS1-Pad22)") (class "Default")
      (node (ref "U4") (pin "22") (pinfunction "CBUS1_22") (pintype "passive+no_connect"))
    )
    (net (code "134") (name "unconnected-(U4-CBUS2-Pad13)") (class "Default")
      (node (ref "U4") (pin "13") (pinfunction "CBUS2_13") (pintype "passive+no_connect"))
    )
    (net (code "135") (name "unconnected-(U4-CBUS3-Pad14)") (class "Default")
      (node (ref "U4") (pin "14") (pinfunction "CBUS3_14") (pintype "passive+no_connect"))
    )
    (net (code "136") (name "unconnected-(U4-CBUS4-Pad12)") (class "Default")
      (node (ref "U4") (pin "12") (pinfunction "CBUS4_12") (pintype "passive+no_connect"))
    )
    (net (code "137") (name "unconnected-(U4-CTS#-Pad11)") (class "Default")
      (node (ref "U4") (pin "11") (pinfunction "CTS#_11") (pintype "passive+no_connect"))
    )
    (net (code "138") (name "unconnected-(U4-DCD#-Pad10)") (class "Default")
      (node (ref "U4") (pin "10") (pinfunction "DCD#_10") (pintype "passive+no_connect"))
    )
    (net (code "139") (name "unconnected-(U4-DSR#-Pad9)") (class "Default")
      (node (ref "U4") (pin "9") (pinfunction "DSR#_9") (pintype "passive+no_connect"))
    )
    (net (code "140") (name "unconnected-(U4-DTR#-Pad2)") (class "Default")
      (node (ref "U4") (pin "2") (pinfunction "DTR#_2") (pintype "passive+no_connect"))
    )
    (net (code "141") (name "unconnected-(U4-NC-Pad8)") (class "Default")
      (node (ref "U4") (pin "8") (pinfunction "NC_8") (pintype "passive+no_connect"))
    )
    (net (code "142") (name "unconnected-(U4-NC-Pad24)") (class "Default")
      (node (ref "U4") (pin "24") (pinfunction "NC_24") (pintype "passive+no_connect"))
    )
    (net (code "143") (name "unconnected-(U4-OSCI-Pad27)") (class "Default")
      (node (ref "U4") (pin "27") (pinfunction "OSCI_27") (pintype "passive+no_connect"))
    )
    (net (code "144") (name "unconnected-(U4-OSCO-Pad28)") (class "Default")
      (node (ref "U4") (pin "28") (pinfunction "OSCO_28") (pintype "passive+no_connect"))
    )
    (net (code "145") (name "unconnected-(U4-RI#-Pad6)") (class "Default")
      (node (ref "U4") (pin "6") (pinfunction "RI#_6") (pintype "passive+no_connect"))
    )
    (net (code "146") (name "unconnected-(U4-RTS#-Pad3)") (class "Default")
      (node (ref "U4") (pin "3") (pinfunction "RTS#_3") (pintype "passive+no_connect"))
    )
    (net (code "147") (name "unconnected-(U5-AIO0-Pad30)") (class "Default")
      (node (ref "U5") (pin "30") (pinfunction "AIO0_30") (pintype "passive+no_connect"))
    )
    (net (code "148") (name "unconnected-(U5-AIO1-Pad35)") (class "Default")
      (node (ref "U5") (pin "35") (pinfunction "AIO1_35") (pintype "passive+no_connect"))
    )
    (net (code "149") (name "unconnected-(U5-GPIO8-Pad31)") (class "Default")
      (node (ref "U5") (pin "31") (pinfunction "GPIO8_31") (pintype "passive+no_connect"))
    )
    (net (code "150") (name "unconnected-(U5-GPIO9-Pad32)") (class "Default")
      (node (ref "U5") (pin "32") (pinfunction "GPIO9_32") (pintype "passive+no_connect"))
    )
    (net (code "151") (name "unconnected-(U5-GPIO10-Pad33)") (class "Default")
      (node (ref "U5") (pin "33") (pinfunction "GPIO10_33") (pintype "passive+no_connect"))
    )
    (net (code "152") (name "unconnected-(U5-GPIO11-Pad34)") (class "Default")
      (node (ref "U5") (pin "34") (pinfunction "GPIO11_34") (pintype "passive+no_connect"))
    )
    (net (code "153") (name "unconnected-(U5-PCM_CLK-Pad7)") (class "Default")
      (node (ref "U5") (pin "7") (pinfunction "PCM_CLK_7") (pintype "passive+no_connect"))
    )
    (net (code "154") (name "unconnected-(U5-PCM_IN-Pad9)") (class "Default")
      (node (ref "U5") (pin "9") (pinfunction "PCM_IN_9") (pintype "passive+no_connect"))
    )
    (net (code "155") (name "unconnected-(U5-PCM_OUT-Pad10)") (class "Default")
      (node (ref "U5") (pin "10") (pinfunction "PCM_OUT_10") (pintype "passive+no_connect"))
    )
    (net (code "156") (name "unconnected-(U5-PCM_SYNC-Pad8)") (class "Default")
      (node (ref "U5") (pin "8") (pinfunction "PCM_SYNC_8") (pintype "passive+no_connect"))
    )
    (net (code "157") (name "unconnected-(U5-UART_CTS-Pad16)") (class "Default")
      (node (ref "U5") (pin "16") (pinfunction "UART_CTS_16") (pintype "passive+no_connect"))
    )
    (net (code "158") (name "unconnected-(U5-UART_RTS-Pad15)") (class "Default")
      (node (ref "U5") (pin "15") (pinfunction "UART_RTS_15") (pintype "passive+no_connect"))
    )
    (net (code "159") (name "unconnected-(U5-USB_D+-Pad17)") (class "Default")
      (node (ref "U5") (pin "17") (pinfunction "USB_D+_17") (pintype "passive+no_connect"))
    )
    (net (code "160") (name "unconnected-(U5-USB_D--Pad18)") (class "Default")
      (node (ref "U5") (pin "18") (pinfunction "USB_D-_18") (pintype "passive+no_connect"))
    )
  )
)
